# EPS_Distribution_LCL-TK.net
KiCad netlist of a schematic drawn in Altium Designer
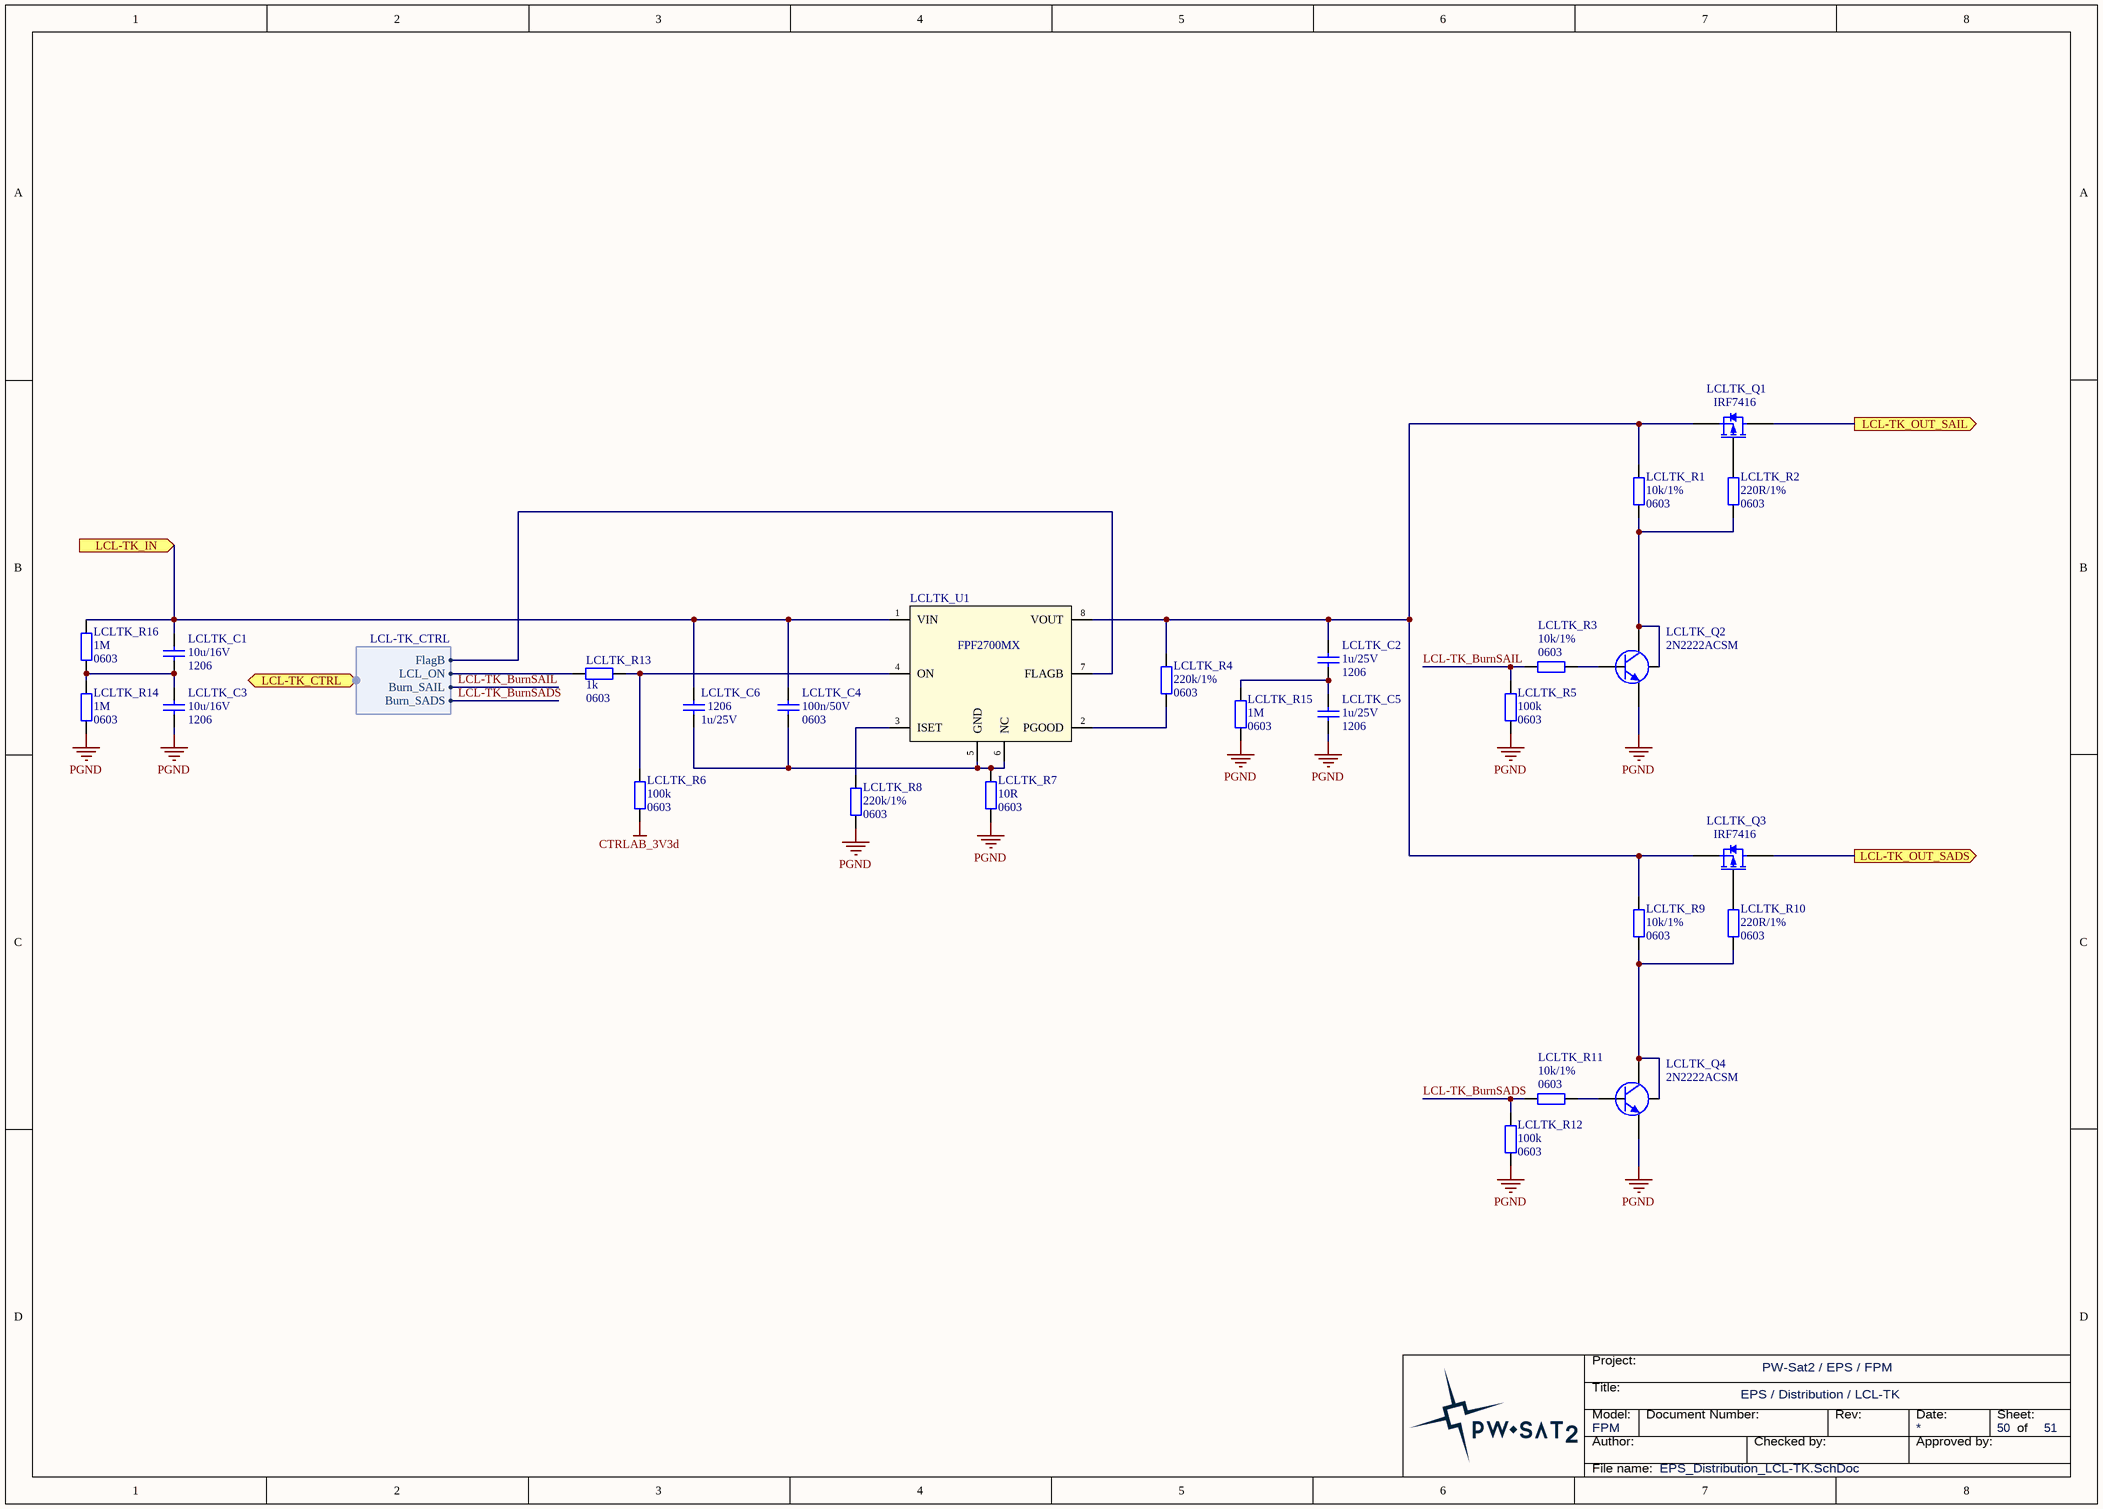
[diagram p0: EPS_Distribution_LCL-TK.SchDoc]

(export (version "E")
  (design (tool "Eeschema 10.0.6"))
  (components
    (comp (ref "LCLTK_C1")
      (value "10u/16V")
      (footprint "SMD_Capacitor_1206")
      (description "Ceramic Cap Kemet COTS 10u/16V X7R 1206")
      (fields
        (field (name "MANUFACTURERPARTNUMBER") "C1206T106K4RACTU")
        (field (name "MANUFACTURER") "Kemet")
        (field (name "PACKGE") "1206")
      )
      (libsource (lib "capacitors") (part "Cer_C1206T106K4RACTU"))
    )
    (comp (ref "LCLTK_C2")
      (value "1u/25V")
      (footprint "SMD_Capacitor_1206")
      (description "Ceramic Cap Kemet COTS 1u/25V X7R 1206")
      (fields
        (field (name "MANUFACTURERPARTNUMBER") "C1206T105K3RALTU")
        (field (name "MANUFACTURER") "Kemet")
        (field (name "PACKAGE") "1206")
      )
      (libsource (lib "capacitors") (part "Cer_C1206T105K3RALTU"))
    )
    (comp (ref "LCLTK_C3")
      (value "10u/16V")
      (footprint "SMD_Capacitor_1206")
      (description "Ceramic Cap Kemet COTS 10u/16V X7R 1206")
      (fields
        (field (name "MANUFACTURERPARTNUMBER") "C1206T106K4RACTU")
        (field (name "MANUFACTURER") "Kemet")
        (field (name "PACKGE") "1206")
      )
      (libsource (lib "capacitors") (part "Cer_C1206T106K4RACTU"))
    )
    (comp (ref "LCLTK_C4")
      (value "100n/50V")
      (footprint "SMD_Capacitor_0603")
      (description "Ceramic Cap Kemet COTS 100n/50V X7R 0603")
      (fields
        (field (name "MANUFACTURER") "Kemet")
        (field (name "MANUFACTURERPARTNUMBER") "C0603T104K5RALTU")
        (field (name "PACKAGE") "0603")
      )
      (libsource (lib "capacitors") (part "Cer_C0603T104K5RALTU"))
    )
    (comp (ref "LCLTK_C5")
      (value "1u/25V")
      (footprint "SMD_Capacitor_1206")
      (description "Ceramic Cap Kemet COTS 1u/25V X7R 1206")
      (fields
        (field (name "MANUFACTURERPARTNUMBER") "C1206T105K3RALTU")
        (field (name "MANUFACTURER") "Kemet")
        (field (name "PACKAGE") "1206")
      )
      (libsource (lib "capacitors") (part "Cer_C1206T105K3RALTU"))
    )
    (comp (ref "LCLTK_C6")
      (value "1u/25V")
      (footprint "SMD_Capacitor_1206")
      (description "Ceramic Cap Kemet COTS 1u/25V X7R 1206")
      (fields
        (field (name "MANUFACTURERPARTNUMBER") "C1206T105K3RALTU")
        (field (name "MANUFACTURER") "Kemet")
        (field (name "PACKAGE") "1206")
      )
      (libsource (lib "capacitors") (part "Cer_C1206T105K3RALTU"))
    )
    (comp (ref "LCLTK_Q1")
      (value "IRF7416")
      (footprint "SOIC-8-N_SSSGDDDD")
      (description "10A/30V HEXFET Power P-MOSFET.")
      (fields (field (name "MANUFACTURER") "International Rectifier"))
      (libsource (lib "transistors") (part "IRF7416"))
    )
    (comp (ref "LCLTK_Q2")
      (value "2N2222ACSM")
      (footprint "LCC1-4_BEC")
      (description "Silicon Planar Epitaxial NPN Transistor.")
      (fields (field (name "MANUFACTURER") "Semelab-TT"))
      (libsource (lib "transistors") (part "2N2222ACSM"))
    )
    (comp (ref "LCLTK_Q3")
      (value "IRF7416")
      (footprint "SOIC-8-N_SSSGDDDD")
      (description "10A/30V HEXFET Power P-MOSFET.")
      (fields (field (name "MANUFACTURER") "International Rectifier"))
      (libsource (lib "transistors") (part "IRF7416"))
    )
    (comp (ref "LCLTK_Q4")
      (value "2N2222ACSM")
      (footprint "LCC1-4_BEC")
      (description "Silicon Planar Epitaxial NPN Transistor.")
      (fields (field (name "MANUFACTURER") "Semelab-TT"))
      (libsource (lib "transistors") (part "2N2222ACSM"))
    )
    (comp (ref "LCLTK_R1")
      (value "10k/1%")
      (footprint "SMD_Resistor_0603")
      (fields (field (name "PACKAGE") "0603"))
      (libsource (lib "") (part "Res_1"))
    )
    (comp (ref "LCLTK_R2")
      (value "220R/1%")
      (footprint "SMD_Resistor_0603")
      (fields (field (name "PACKAGE") "0603"))
      (libsource (lib "") (part "Res_1"))
    )
    (comp (ref "LCLTK_R3")
      (value "10k/1%")
      (footprint "SMD_Resistor_0603")
      (fields (field (name "PACKAGE") "0603"))
      (libsource (lib "resistors") (part "Res"))
    )
    (comp (ref "LCLTK_R4")
      (value "220k/1%")
      (footprint "SMD_Resistor_0603")
      (fields (field (name "PACKAGE") "0603"))
      (libsource (lib "") (part "Res_1"))
    )
    (comp (ref "LCLTK_R5")
      (value "100k")
      (footprint "SMD_Resistor_0603")
      (fields (field (name "PACKAGE") "0603"))
      (libsource (lib "") (part "Res_1"))
    )
    (comp (ref "LCLTK_R6")
      (value "100k")
      (footprint "SMD_Resistor_0603")
      (fields (field (name "PACKAGE") "0603"))
      (libsource (lib "") (part "Res_1"))
    )
    (comp (ref "LCLTK_R7")
      (value "10R")
      (footprint "SMD_Resistor_0603")
      (fields (field (name "PACKAGE") "0603"))
      (libsource (lib "") (part "Res_1"))
    )
    (comp (ref "LCLTK_R8")
      (value "220k/1%")
      (footprint "SMD_Resistor_0603")
      (fields (field (name "PACKAGE") "0603"))
      (libsource (lib "") (part "Res_1"))
    )
    (comp (ref "LCLTK_R9")
      (value "10k/1%")
      (footprint "SMD_Resistor_0603")
      (fields (field (name "PACKAGE") "0603"))
      (libsource (lib "") (part "Res_1"))
    )
    (comp (ref "LCLTK_R10")
      (value "220R/1%")
      (footprint "SMD_Resistor_0603")
      (fields (field (name "PACKAGE") "0603"))
      (libsource (lib "") (part "Res_1"))
    )
    (comp (ref "LCLTK_R11")
      (value "10k/1%")
      (footprint "SMD_Resistor_0603")
      (fields (field (name "PACKAGE") "0603"))
      (libsource (lib "resistors") (part "Res"))
    )
    (comp (ref "LCLTK_R12")
      (value "100k")
      (footprint "SMD_Resistor_0603")
      (fields (field (name "PACKAGE") "0603"))
      (libsource (lib "") (part "Res_1"))
    )
    (comp (ref "LCLTK_R13")
      (value "1k")
      (footprint "SMD_Resistor_0603")
      (fields (field (name "PACKAGE") "0603"))
      (libsource (lib "resistors") (part "Res"))
    )
    (comp (ref "LCLTK_R14")
      (value "1M")
      (footprint "SMD_Resistor_0603")
      (fields (field (name "PACKAGE") "0603"))
      (libsource (lib "") (part "Res_1"))
    )
    (comp (ref "LCLTK_R15")
      (value "1M")
      (footprint "SMD_Resistor_0603")
      (fields (field (name "PACKAGE") "0603"))
      (libsource (lib "") (part "Res_1"))
    )
    (comp (ref "LCLTK_R16")
      (value "1M")
      (footprint "SMD_Resistor_0603")
      (fields (field (name "PACKAGE") "0603"))
      (libsource (lib "") (part "Res_1"))
    )
    (comp (ref "LCLTK_U1")
      (value "FPF2700MX")
      (footprint "SOIC-8-N")
      (description "Adj over-current protection 0.4-2A, Load Switch")
      (fields (field (name "MANUFACTURER") "Fairchild Semiconductor"))
      (libsource (lib "microcircuits") (part "FPF2700MX"))
    )
  )
  (nets
    (net (code "2") (name "/FlagB") (class "Default")
      (node (ref "LCLTK_U1") (pin "7") (pinfunction "FLAGB_7") (pintype "passive"))
    )
    (net (code "3") (name "/LCL-TK_BurnSADS") (class "Default")
      (node (ref "LCLTK_R11") (pin "2") (pinfunction "2_2") (pintype "passive"))
      (node (ref "LCLTK_R12") (pin "2") (pinfunction "2_2") (pintype "passive"))
    )
    (net (code "4") (name "/LCL-TK_BurnSAIL") (class "Default")
      (node (ref "LCLTK_R3") (pin "2") (pinfunction "2_2") (pintype "passive"))
      (node (ref "LCLTK_R5") (pin "2") (pinfunction "2_2") (pintype "passive"))
    )
    (net (code "5") (name "/LCL-TK_IN") (class "Default")
      (node (ref "LCLTK_C1") (pin "1") (pinfunction "1_1") (pintype "passive"))
      (node (ref "LCLTK_C4") (pin "1") (pinfunction "1_1") (pintype "passive"))
      (node (ref "LCLTK_C6") (pin "1") (pinfunction "1_1") (pintype "passive"))
      (node (ref "LCLTK_R16") (pin "2") (pinfunction "2_2") (pintype "passive"))
      (node (ref "LCLTK_U1") (pin "1") (pinfunction "VIN_1") (pintype "passive"))
    )
    (net (code "6") (name "/LCL-TK_OUT_SADS") (class "Default")
      (node (ref "LCLTK_Q3") (pin "D") (pinfunction "D_D") (pintype "passive"))
    )
    (net (code "7") (name "/LCL-TK_OUT_SAIL") (class "Default")
      (node (ref "LCLTK_Q1") (pin "D") (pinfunction "D_D") (pintype "passive"))
    )
    (net (code "8") (name "/LCL_ON") (class "Default")
      (node (ref "LCLTK_R13") (pin "2") (pinfunction "2_2") (pintype "passive"))
    )
    (net (code "10") (name "CTRLAB_3V3d") (class "Default")
      (node (ref "LCLTK_R6") (pin "1") (pinfunction "1_1") (pintype "passive"))
    )
    (net (code "11") (name "Net-(LCLTK_C1-Pad2)") (class "Default")
      (node (ref "LCLTK_C1") (pin "2") (pinfunction "2_2") (pintype "passive"))
      (node (ref "LCLTK_C3") (pin "1") (pinfunction "1_1") (pintype "passive"))
      (node (ref "LCLTK_R14") (pin "2") (pinfunction "2_2") (pintype "passive"))
      (node (ref "LCLTK_R16") (pin "1") (pinfunction "1_1") (pintype "passive"))
    )
    (net (code "12") (name "Net-(LCLTK_C2-Pad2)") (class "Default")
      (node (ref "LCLTK_C2") (pin "2") (pinfunction "2_2") (pintype "passive"))
      (node (ref "LCLTK_C5") (pin "1") (pinfunction "1_1") (pintype "passive"))
      (node (ref "LCLTK_R15") (pin "2") (pinfunction "2_2") (pintype "passive"))
    )
    (net (code "13") (name "Net-(LCLTK_Q1-PadG)") (class "Default")
      (node (ref "LCLTK_Q1") (pin "G") (pinfunction "G_G") (pintype "passive"))
      (node (ref "LCLTK_R2") (pin "2") (pinfunction "2_2") (pintype "passive"))
    )
    (net (code "14") (name "Net-(LCLTK_Q2-PadB)") (class "Default")
      (node (ref "LCLTK_Q2") (pin "B") (pinfunction "B_B") (pintype "passive"))
      (node (ref "LCLTK_R3") (pin "1") (pinfunction "1_1") (pintype "passive"))
    )
    (net (code "15") (name "Net-(LCLTK_Q2-PadC)") (class "Default")
      (node (ref "LCLTK_Q2") (pin "C") (pinfunction "C_C") (pintype "passive"))
      (node (ref "LCLTK_Q2") (pin "Shield") (pinfunction "Shield_Shield") (pintype "passive"))
      (node (ref "LCLTK_R1") (pin "1") (pinfunction "1_1") (pintype "passive"))
      (node (ref "LCLTK_R2") (pin "1") (pinfunction "1_1") (pintype "passive"))
    )
    (net (code "16") (name "Net-(LCLTK_Q3-PadG)") (class "Default")
      (node (ref "LCLTK_Q3") (pin "G") (pinfunction "G_G") (pintype "passive"))
      (node (ref "LCLTK_R10") (pin "2") (pinfunction "2_2") (pintype "passive"))
    )
    (net (code "17") (name "Net-(LCLTK_Q4-PadB)") (class "Default")
      (node (ref "LCLTK_Q4") (pin "B") (pinfunction "B_B") (pintype "passive"))
      (node (ref "LCLTK_R11") (pin "1") (pinfunction "1_1") (pintype "passive"))
    )
    (net (code "18") (name "Net-(LCLTK_Q4-PadC)") (class "Default")
      (node (ref "LCLTK_Q4") (pin "C") (pinfunction "C_C") (pintype "passive"))
      (node (ref "LCLTK_Q4") (pin "Shield") (pinfunction "Shield_Shield") (pintype "passive"))
      (node (ref "LCLTK_R10") (pin "1") (pinfunction "1_1") (pintype "passive"))
      (node (ref "LCLTK_R9") (pin "1") (pinfunction "1_1") (pintype "passive"))
    )
    (net (code "19") (name "Net-(LCLTK_U1-GND)") (class "Default")
      (node (ref "LCLTK_C4") (pin "2") (pinfunction "2_2") (pintype "passive"))
      (node (ref "LCLTK_C6") (pin "2") (pinfunction "2_2") (pintype "passive"))
      (node (ref "LCLTK_R7") (pin "2") (pinfunction "2_2") (pintype "passive"))
      (node (ref "LCLTK_U1") (pin "5") (pinfunction "GND_5") (pintype "passive"))
      (node (ref "LCLTK_U1") (pin "6") (pinfunction "NC_6") (pintype "passive"))
    )
    (net (code "20") (name "Net-(LCLTK_U1-ISET)") (class "Default")
      (node (ref "LCLTK_R8") (pin "2") (pinfunction "2_2") (pintype "passive"))
      (node (ref "LCLTK_U1") (pin "3") (pinfunction "ISET_3") (pintype "passive"))
    )
    (net (code "21") (name "Net-(LCLTK_U1-ON)") (class "Default")
      (node (ref "LCLTK_R13") (pin "1") (pinfunction "1_1") (pintype "passive"))
      (node (ref "LCLTK_R6") (pin "2") (pinfunction "2_2") (pintype "passive"))
      (node (ref "LCLTK_U1") (pin "4") (pinfunction "ON_4") (pintype "passive"))
    )
    (net (code "22") (name "Net-(LCLTK_U1-PGOOD)") (class "Default")
      (node (ref "LCLTK_R4") (pin "1") (pinfunction "1_1") (pintype "passive"))
      (node (ref "LCLTK_U1") (pin "2") (pinfunction "PGOOD_2") (pintype "passive"))
    )
    (net (code "23") (name "Net-(LCLTK_U1-VOUT)") (class "Default")
      (node (ref "LCLTK_C2") (pin "1") (pinfunction "1_1") (pintype "passive"))
      (node (ref "LCLTK_Q1") (pin "S") (pinfunction "S_S") (pintype "passive"))
      (node (ref "LCLTK_Q3") (pin "S") (pinfunction "S_S") (pintype "passive"))
      (node (ref "LCLTK_R1") (pin "2") (pinfunction "2_2") (pintype "passive"))
      (node (ref "LCLTK_R4") (pin "2") (pinfunction "2_2") (pintype "passive"))
      (node (ref "LCLTK_R9") (pin "2") (pinfunction "2_2") (pintype "passive"))
      (node (ref "LCLTK_U1") (pin "8") (pinfunction "VOUT_8") (pintype "passive"))
    )
    (net (code "24") (name "PGND") (class "Default")
      (node (ref "LCLTK_C3") (pin "2") (pinfunction "2_2") (pintype "passive"))
      (node (ref "LCLTK_C5") (pin "2") (pinfunction "2_2") (pintype "passive"))
      (node (ref "LCLTK_Q2") (pin "E") (pinfunction "E_E") (pintype "passive"))
      (node (ref "LCLTK_Q4") (pin "E") (pinfunction "E_E") (pintype "passive"))
      (node (ref "LCLTK_R12") (pin "1") (pinfunction "1_1") (pintype "passive"))
      (node (ref "LCLTK_R14") (pin "1") (pinfunction "1_1") (pintype "passive"))
      (node (ref "LCLTK_R15") (pin "1") (pinfunction "1_1") (pintype "passive"))
      (node (ref "LCLTK_R5") (pin "1") (pinfunction "1_1") (pintype "passive"))
      (node (ref "LCLTK_R7") (pin "1") (pinfunction "1_1") (pintype "passive"))
      (node (ref "LCLTK_R8") (pin "1") (pinfunction "1_1") (pintype "passive"))
    )
  )
)
